# Sheet1.net
KiCad netlist of a schematic drawn in Altium Designer
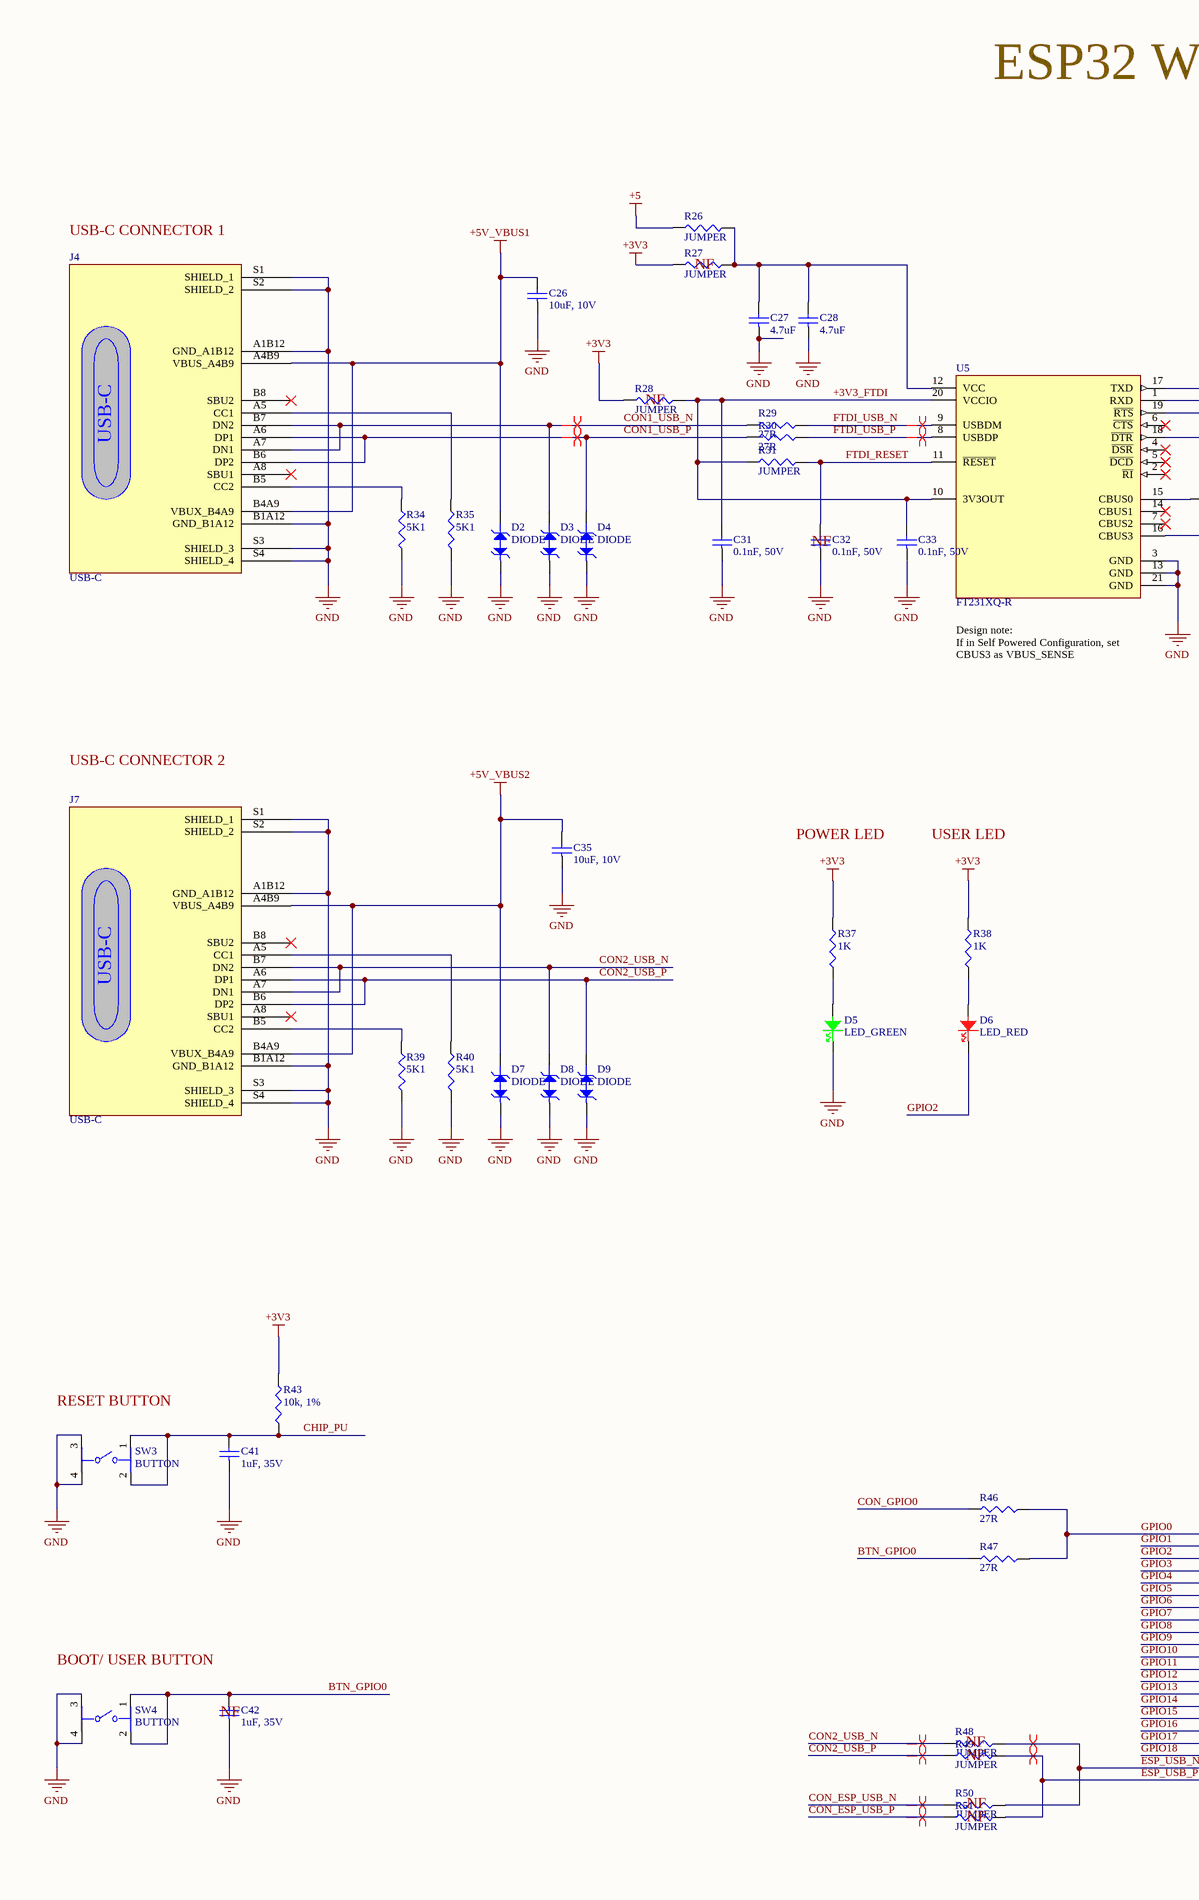
[diagram p0: Sheet1.SchDoc, left]
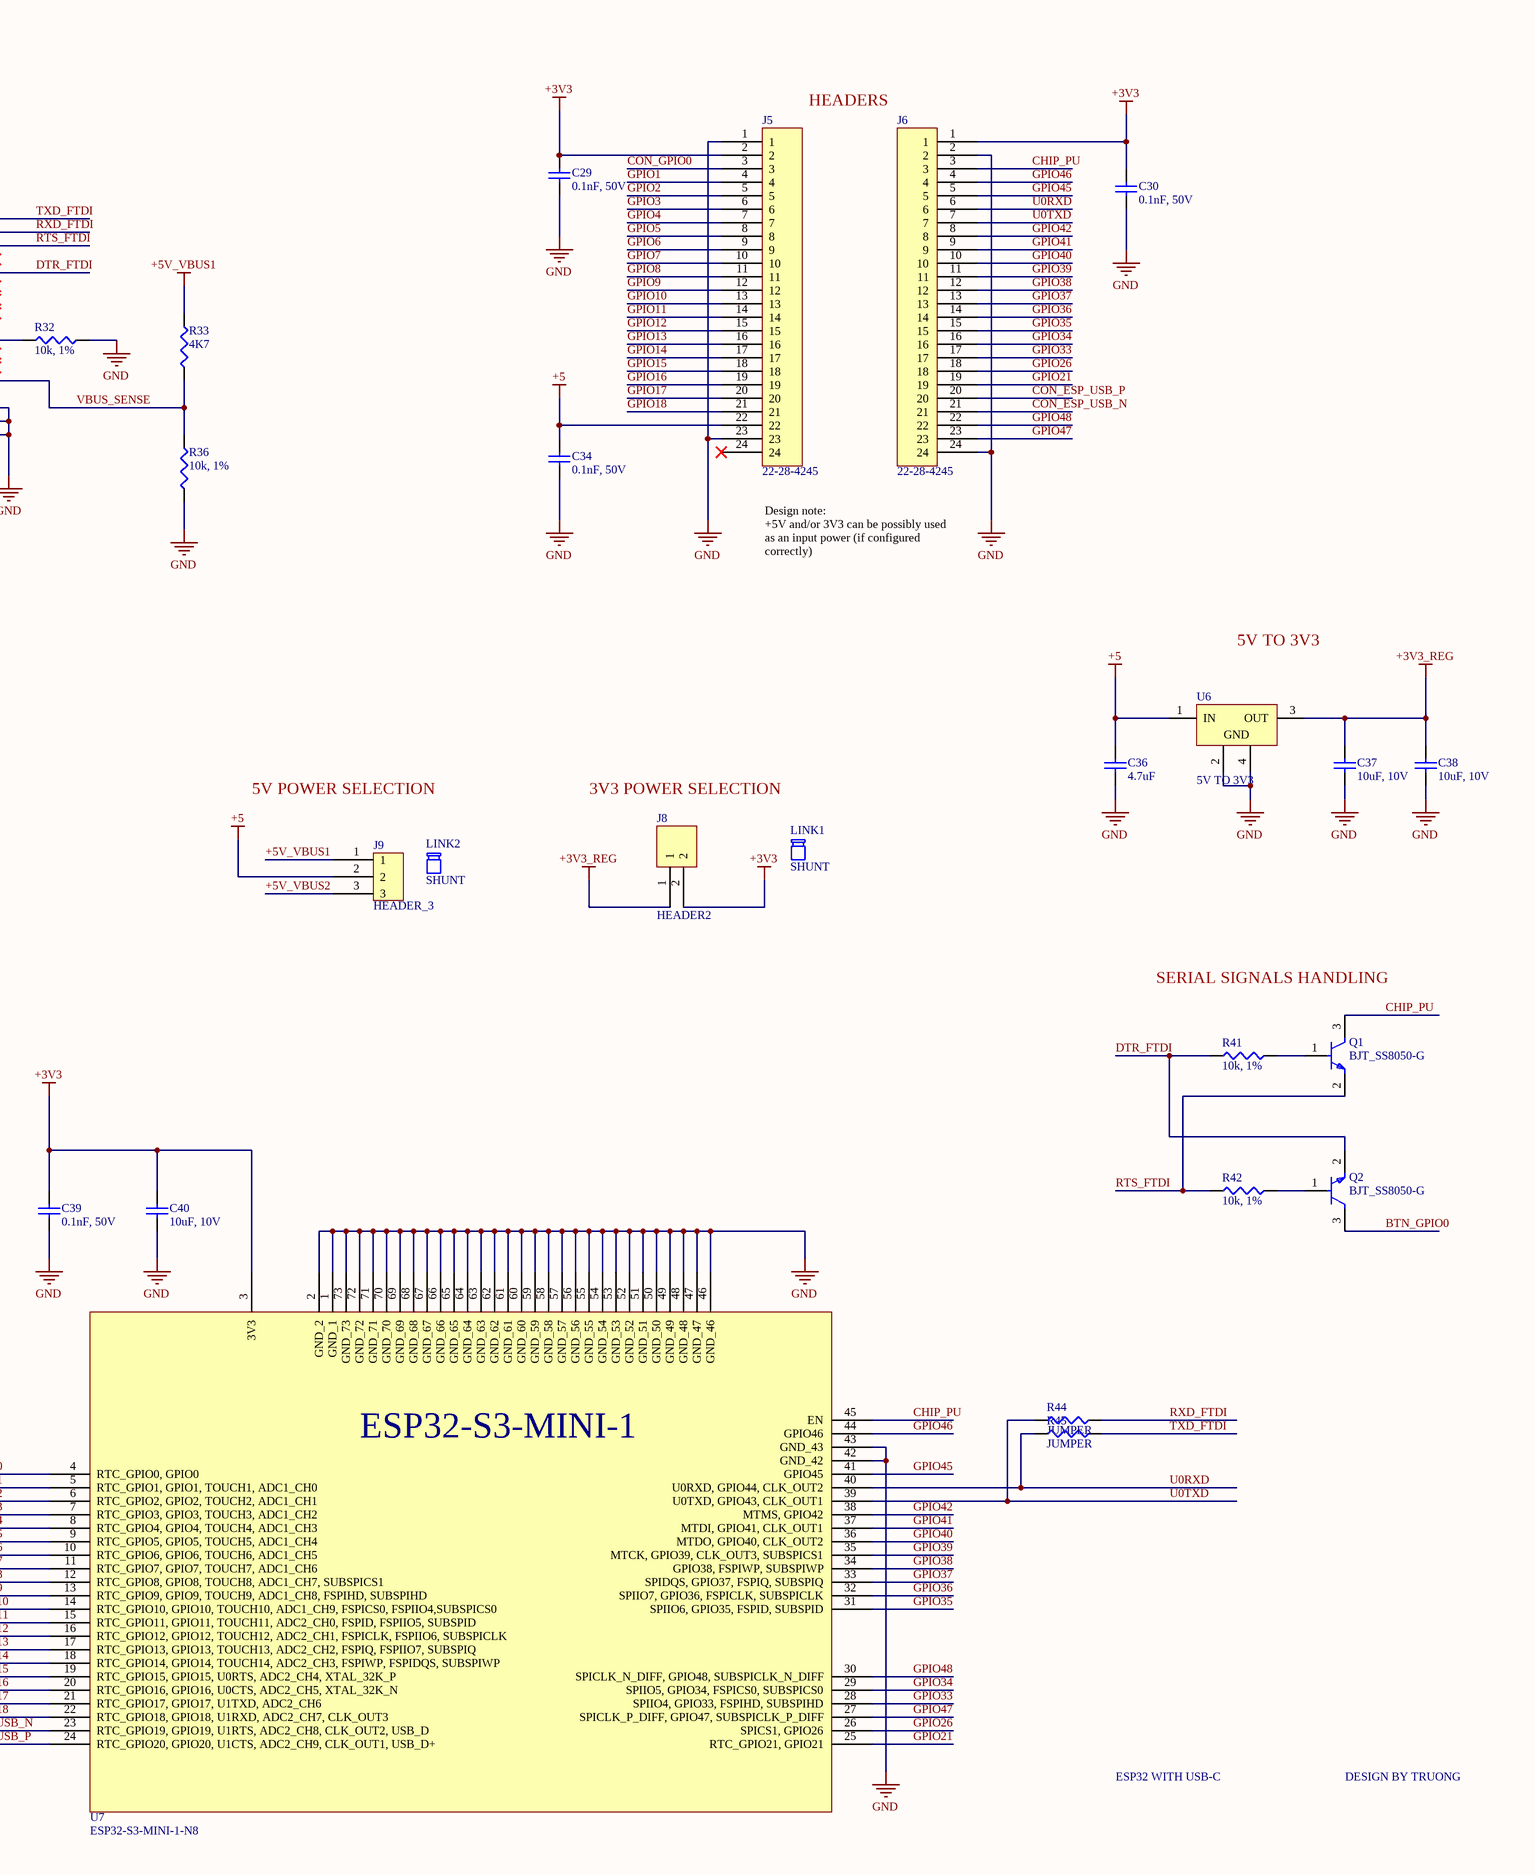
[diagram p1: Sheet1.SchDoc, right]

(export (version "E")
  (design (tool "Eeschema 10.0.6"))
  (components
    (comp (ref "C26")
      (value "10uF, 10V")
      (footprint "CAPC1005X70N")
      (description "CAP CER 10UF 10V X5R 0402")
      (fields
        (field (name "MANUFACTURER") "Samsung Electro-Mechanics")
        (field (name "MANUFACTURER PART NUMBER") "CL05A106MP5NUNC")
      )
      (libsource (lib "ESP32_CUSTOM_SCH.PrjPcb") (part "CL05A106MP5NUNC"))
    )
    (comp (ref "C27")
      (value "4.7uF")
      (footprint "CAPC1005X70N")
      (description "CAP CER 4.7UF 16V X5R 0402")
      (fields
        (field (name "MANUFACTURER") "Samsung Electro-Mechanics")
        (field (name "MANUFACTURER PART NUMBER") "CL05A475MO5NUNC")
      )
      (libsource (lib "ESP32_CUSTOM_SCH.PrjPcb") (part "CL05A475MO5NUNC"))
    )
    (comp (ref "C28")
      (value "4.7uF")
      (footprint "CAPC1005X70N")
      (description "CAP CER 4.7UF 16V X5R 0402")
      (fields
        (field (name "MANUFACTURER") "Samsung Electro-Mechanics")
        (field (name "MANUFACTURER PART NUMBER") "CL05A475MO5NUNC")
      )
      (libsource (lib "ESP32_CUSTOM_SCH.PrjPcb") (part "CL05A475MO5NUNC"))
    )
    (comp (ref "C29")
      (value "0.1nF, 50V")
      (footprint "CAPC1005X70N")
      (description "CAP CER 0.1UF 50V X7R 0402")
      (fields
        (field (name "MANUFACTURER") "Samsung Electro-Mechanics")
        (field (name "MANUFACTURER PART NUMBER") "CL05B104KB5NNWC")
      )
      (libsource (lib "ESP32_CUSTOM_SCH.PrjPcb") (part "CL05B104KB5NNWC"))
    )
    (comp (ref "C30")
      (value "0.1nF, 50V")
      (footprint "CAPC1005X70N")
      (description "CAP CER 0.1UF 50V X7R 0402")
      (fields
        (field (name "MANUFACTURER") "Samsung Electro-Mechanics")
        (field (name "MANUFACTURER PART NUMBER") "CL05B104KB5NNWC")
      )
      (libsource (lib "ESP32_CUSTOM_SCH.PrjPcb") (part "CL05B104KB5NNWC"))
    )
    (comp (ref "C31")
      (value "0.1nF, 50V")
      (footprint "CAPC1005X70N")
      (description "CAP CER 0.1UF 50V X7R 0402")
      (fields
        (field (name "MANUFACTURER") "Samsung Electro-Mechanics")
        (field (name "MANUFACTURER PART NUMBER") "CL05B104KB5NNWC")
      )
      (libsource (lib "ESP32_CUSTOM_SCH.PrjPcb") (part "CL05B104KB5NNWC"))
    )
    (comp (ref "C32")
      (value "0.1nF, 50V")
      (footprint "CAPC1005X70N")
      (description "CAP CER 0.1UF 50V X7R 0402")
      (fields
        (field (name "MANUFACTURER") "Samsung Electro-Mechanics")
        (field (name "MANUFACTURER PART NUMBER") "CL05B104KB5NNWC")
      )
      (libsource (lib "ESP32_CUSTOM_SCH.PrjPcb") (part "CL05B104KB5NNWC"))
    )
    (comp (ref "C33")
      (value "0.1nF, 50V")
      (footprint "CAPC1005X70N")
      (description "CAP CER 0.1UF 50V X7R 0402")
      (fields
        (field (name "MANUFACTURER") "Samsung Electro-Mechanics")
        (field (name "MANUFACTURER PART NUMBER") "CL05B104KB5NNWC")
      )
      (libsource (lib "ESP32_CUSTOM_SCH.PrjPcb") (part "CL05B104KB5NNWC"))
    )
    (comp (ref "C34")
      (value "0.1nF, 50V")
      (footprint "CAPC1005X70N")
      (description "CAP CER 0.1UF 50V X7R 0402")
      (fields
        (field (name "MANUFACTURER") "Samsung Electro-Mechanics")
        (field (name "MANUFACTURER PART NUMBER") "CL05B104KB5NNWC")
      )
      (libsource (lib "ESP32_CUSTOM_SCH.PrjPcb") (part "CL05B104KB5NNWC"))
    )
    (comp (ref "C35")
      (value "10uF, 10V")
      (footprint "CAPC1005X70N")
      (description "CAP CER 10UF 10V X5R 0402")
      (fields
        (field (name "MANUFACTURER") "Samsung Electro-Mechanics")
        (field (name "MANUFACTURER PART NUMBER") "CL05A106MP5NUNC")
      )
      (libsource (lib "ESP32_CUSTOM_SCH.PrjPcb") (part "CL05A106MP5NUNC"))
    )
    (comp (ref "C36")
      (value "4.7uF")
      (footprint "CAPC1005X70N")
      (description "CAP CER 4.7UF 16V X5R 0402")
      (fields
        (field (name "MANUFACTURER") "Samsung Electro-Mechanics")
        (field (name "MANUFACTURER PART NUMBER") "CL05A475MO5NUNC")
      )
      (libsource (lib "ESP32_CUSTOM_SCH.PrjPcb") (part "CL05A475MO5NUNC"))
    )
    (comp (ref "C37")
      (value "10uF, 10V")
      (footprint "CAPC1005X70N")
      (description "CAP CER 10UF 10V X5R 0402")
      (fields
        (field (name "MANUFACTURER") "Samsung Electro-Mechanics")
        (field (name "MANUFACTURER PART NUMBER") "CL05A106MP5NUNC")
      )
      (libsource (lib "ESP32_CUSTOM_SCH.PrjPcb") (part "CL05A106MP5NUNC"))
    )
    (comp (ref "C38")
      (value "10uF, 10V")
      (footprint "CAPC1005X70N")
      (description "CAP CER 10UF 10V X5R 0402")
      (fields
        (field (name "MANUFACTURER") "Samsung Electro-Mechanics")
        (field (name "MANUFACTURER PART NUMBER") "CL05A106MP5NUNC")
      )
      (libsource (lib "ESP32_CUSTOM_SCH.PrjPcb") (part "CL05A106MP5NUNC"))
    )
    (comp (ref "C39")
      (value "0.1nF, 50V")
      (footprint "CAPC1005X70N")
      (description "CAP CER 0.1UF 50V X7R 0402")
      (fields
        (field (name "MANUFACTURER") "Samsung Electro-Mechanics")
        (field (name "MANUFACTURER PART NUMBER") "CL05B104KB5NNWC")
      )
      (libsource (lib "ESP32_CUSTOM_SCH.PrjPcb") (part "CL05B104KB5NNWC"))
    )
    (comp (ref "C40")
      (value "10uF, 10V")
      (footprint "CAPC1005X70N")
      (description "CAP CER 10UF 10V X5R 0402")
      (fields
        (field (name "MANUFACTURER") "Samsung Electro-Mechanics")
        (field (name "MANUFACTURER PART NUMBER") "CL05A106MP5NUNC")
      )
      (libsource (lib "ESP32_CUSTOM_SCH.PrjPcb") (part "CL05A106MP5NUNC"))
    )
    (comp (ref "C41")
      (value "1uF, 35V")
      (footprint "CAPC1005X70N")
      (description "CAP CER 1UF 35V X5R 0402")
      (fields
        (field (name "MANUFACTURER") "Murata")
        (field (name "MANUFACTURER PART NUMBER") "GRM155R6YA105KE11D")
      )
      (libsource (lib "ESP32_CUSTOM_SCH.PrjPcb") (part "GRM155R6YA105KE11D"))
    )
    (comp (ref "C42")
      (value "1uF, 35V")
      (footprint "CAPC1005X70N")
      (description "CAP CER 1UF 35V X5R 0402")
      (fields
        (field (name "MANUFACTURER") "Murata")
        (field (name "MANUFACTURER PART NUMBER") "GRM155R6YA105KE11D")
      )
      (libsource (lib "ESP32_CUSTOM_SCH.PrjPcb") (part "GRM155R6YA105KE11D"))
    )
    (comp (ref "D2")
      (value "DIODE")
      (footprint "SOD882")
      (description "TVS DIODE 5.3VWM 12VC SOD882")
      (fields
        (field (name "MANUFACTURER") "Littelfuse")
        (field (name "MANUFACTURER PART NUMBER") "AQ3045-01ETG")
      )
      (libsource (lib "ESP32_CUSTOM_SCH.PrjPcb") (part "AQ3045-01ETG"))
    )
    (comp (ref "D3")
      (value "DIODE")
      (footprint "SOD882")
      (description "TVS DIODE 5.3VWM 12VC SOD882")
      (fields
        (field (name "MANUFACTURER") "Littelfuse")
        (field (name "MANUFACTURER PART NUMBER") "AQ3045-01ETG")
      )
      (libsource (lib "ESP32_CUSTOM_SCH.PrjPcb") (part "AQ3045-01ETG"))
    )
    (comp (ref "D4")
      (value "DIODE")
      (footprint "SOD882")
      (description "TVS DIODE 5.3VWM 12VC SOD882")
      (fields
        (field (name "MANUFACTURER") "Littelfuse")
        (field (name "MANUFACTURER PART NUMBER") "AQ3045-01ETG")
      )
      (libsource (lib "ESP32_CUSTOM_SCH.PrjPcb") (part "AQ3045-01ETG"))
    )
    (comp (ref "D5")
      (value "LED_GREEN")
      (footprint "LED0402_GREEN")
      (description "LED GREEN 0402 SMD")
      (fields
        (field (name "MANUFACTURER") "Vishay")
        (field (name "MANUFACTURER PART NUMBER") "VLMTG1500-GS08")
      )
      (libsource (lib "ESP32_CUSTOM_SCH.PrjPcb") (part "VLMTG1500-GS08"))
    )
    (comp (ref "D6")
      (value "LED_RED")
      (footprint "LED0402_RED")
      (description "LED RED 0402 SMD")
      (fields
        (field (name "MANUFACTURER") "Vishay")
        (field (name "MANUFACTURER PART NUMBER") "VLMS1500-GS08")
      )
      (libsource (lib "ESP32_CUSTOM_SCH.PrjPcb") (part "VLMS1500-GS08"))
    )
    (comp (ref "D7")
      (value "DIODE")
      (footprint "SOD882")
      (description "TVS DIODE 5.3VWM 12VC SOD882")
      (fields
        (field (name "MANUFACTURER") "Littelfuse")
        (field (name "MANUFACTURER PART NUMBER") "AQ3045-01ETG")
      )
      (libsource (lib "ESP32_CUSTOM_SCH.PrjPcb") (part "AQ3045-01ETG"))
    )
    (comp (ref "D8")
      (value "DIODE")
      (footprint "SOD882")
      (description "TVS DIODE 5.3VWM 12VC SOD882")
      (fields
        (field (name "MANUFACTURER") "Littelfuse")
        (field (name "MANUFACTURER PART NUMBER") "AQ3045-01ETG")
      )
      (libsource (lib "ESP32_CUSTOM_SCH.PrjPcb") (part "AQ3045-01ETG"))
    )
    (comp (ref "D9")
      (value "DIODE")
      (footprint "SOD882")
      (description "TVS DIODE 5.3VWM 12VC SOD882")
      (fields
        (field (name "MANUFACTURER") "Littelfuse")
        (field (name "MANUFACTURER PART NUMBER") "AQ3045-01ETG")
      )
      (libsource (lib "ESP32_CUSTOM_SCH.PrjPcb") (part "AQ3045-01ETG"))
    )
    (comp (ref "J4")
      (value "USB-C")
      (footprint "FP-2171790001-MFG")
      (description "CONN RCP USB2.0 TYP C 24P SMD RA")
      (fields (field (name "MANUFACTURER") "Molex") (field (name "MANUFACTURER PART NUMBER") "217179-0001"))
      (libsource (lib "ESP32_CUSTOM_SCH.PrjPcb") (part "217179-0001"))
    )
    (comp (ref "J5")
      (value "22-28-4245")
      (footprint "HDR_1X24_2.55MM")
      (description "CONN HEADER VERT 24POS 2.54MM")
      (fields (field (name "MANUFACTURER") "Molex") (field (name "LCSC PART NUMBER") "C7145888"))
      (libsource (lib "") (part "22-28-4245_1"))
    )
    (comp (ref "J6")
      (value "22-28-4245")
      (footprint "HDR_1X24_2.55MM")
      (description "CONN HEADER VERT 24POS 2.54MM")
      (fields (field (name "MANUFACTURER") "Molex") (field (name "LCSC PART NUMBER") "C7145888"))
      (libsource (lib "ESP32_CUSTOM_SCH.PrjPcb") (part "22-28-4245"))
    )
    (comp (ref "J7")
      (value "USB-C")
      (footprint "FP-2171790001-MFG")
      (description "CONN RCP USB2.0 TYP C 24P SMD RA")
      (fields (field (name "MANUFACTURER") "Molex") (field (name "MANUFACTURER PART NUMBER") "217179-0001"))
      (libsource (lib "ESP32_CUSTOM_SCH.PrjPcb") (part "217179-0001"))
    )
    (comp (ref "J8")
      (value "HEADER2")
      (footprint "HDR_1X2_1.27MM")
      (description "CONN HEADER VERT 2POS 1.27MM")
      (fields
        (field (name "MANUFACTURER") "Samtec")
        (field (name "MANUFACTURER PART NUMBER") "FTS-102-01-L-S")
      )
      (libsource (lib "ESP32_CUSTOM_SCH.PrjPcb") (part "FTS-102-01-L-S"))
    )
    (comp (ref "J9")
      (value "HEADER_3")
      (footprint "HDR_1X3_1.27MM")
      (description "CONN HEADER VERT 3POS 1.27MM")
      (fields
        (field (name "MANUFACTURER") "Samtec")
        (field (name "MANUFACTURER PART NUMBER") "FTS-103-01-F-S")
      )
      (libsource (lib "ESP32_CUSTOM_SCH.PrjPcb") (part "FTS-103-01-F-S"))
    )
    (comp (ref "LINK1")
      (value "SHUNT")
      (description "CONN SHUNT 1.27MM RED")
      (fields (field (name "MANUFACTURER") "Harwin") (field (name "MANUFACTURER PART NUMBER") "M50-1920005"))
      (libsource (lib "ESP32_CUSTOM_SCH.PrjPcb") (part "M50-1920005"))
    )
    (comp (ref "LINK2")
      (value "SHUNT")
      (description "CONN SHUNT 1.27MM RED")
      (fields (field (name "MANUFACTURER") "Harwin") (field (name "MANUFACTURER PART NUMBER") "M50-1920005"))
      (libsource (lib "ESP32_CUSTOM_SCH.PrjPcb") (part "M50-1920005"))
    )
    (comp (ref "Q1")
      (value "BJT_SS8050-G")
      (footprint "FP-SS8050-G-IPC_B")
      (description "TRANS NPN 25V 1.5A SOT-23-3")
      (fields (field (name "MANUFACTURER") "Comchip") (field (name "MANUFACTURER PART NUMBER") "SS8050-G"))
      (libsource (lib "ESP32_CUSTOM_SCH.PrjPcb") (part "SS8050-G"))
    )
    (comp (ref "Q2")
      (value "BJT_SS8050-G")
      (footprint "FP-SS8050-G-IPC_B")
      (description "TRANS NPN 25V 1.5A SOT-23-3")
      (fields (field (name "MANUFACTURER") "Comchip") (field (name "MANUFACTURER PART NUMBER") "SS8050-G"))
      (libsource (lib "ESP32_CUSTOM_SCH.PrjPcb") (part "SS8050-G"))
    )
    (comp (ref "R26")
      (value "JUMPER")
      (footprint "RESC1005X40N")
      (description "RES 0 OHM JUMPER 1/16W 0402")
      (fields
        (field (name "MANUFACTURER") "Yageo Group")
        (field (name "MANUFACTURER PART NUMBER") "RC0402JR-070RL")
      )
      (libsource (lib "ESP32_CUSTOM_SCH.PrjPcb") (part "RC0402JR-070RL"))
    )
    (comp (ref "R27")
      (value "JUMPER")
      (footprint "RESC1005X40N")
      (description "RES 0 OHM JUMPER 1/16W 0402")
      (fields
        (field (name "MANUFACTURER") "Yageo Group")
        (field (name "MANUFACTURER PART NUMBER") "RC0402JR-070RL")
      )
      (libsource (lib "ESP32_CUSTOM_SCH.PrjPcb") (part "RC0402JR-070RL"))
    )
    (comp (ref "R28")
      (value "JUMPER")
      (footprint "RESC1005X40N")
      (description "RES 0 OHM JUMPER 1/16W 0402")
      (fields
        (field (name "MANUFACTURER") "Yageo Group")
        (field (name "MANUFACTURER PART NUMBER") "RC0402JR-070RL")
      )
      (libsource (lib "ESP32_CUSTOM_SCH.PrjPcb") (part "RC0402JR-070RL"))
    )
    (comp (ref "R29")
      (value "27R")
      (footprint "RESC1005X40N")
      (description "RES 27 OHM 1% 1/16W 0402")
      (fields
        (field (name "MANUFACTURER") "Yageo Group")
        (field (name "MANUFACTURER PART NUMBER") "RC0402FR-0727RL")
      )
      (libsource (lib "ESP32_CUSTOM_SCH.PrjPcb") (part "RC0402FR-0727RL"))
    )
    (comp (ref "R30")
      (value "27R")
      (footprint "RESC1005X40N")
      (description "RES 27 OHM 1% 1/16W 0402")
      (fields
        (field (name "MANUFACTURER") "Yageo Group")
        (field (name "MANUFACTURER PART NUMBER") "RC0402FR-0727RL")
      )
      (libsource (lib "ESP32_CUSTOM_SCH.PrjPcb") (part "RC0402FR-0727RL"))
    )
    (comp (ref "R31")
      (value "JUMPER")
      (footprint "RESC1005X40N")
      (description "RES 0 OHM JUMPER 1/16W 0402")
      (fields
        (field (name "MANUFACTURER") "Yageo Group")
        (field (name "MANUFACTURER PART NUMBER") "RC0402JR-070RL")
      )
      (libsource (lib "ESP32_CUSTOM_SCH.PrjPcb") (part "RC0402JR-070RL"))
    )
    (comp (ref "R32")
      (value "10k, 1%")
      (footprint "RESC1005X40N")
      (description "RES 10K OHM 1% 1/16W 0402")
      (fields
        (field (name "MANUFACTURER") "Yageo Group")
        (field (name "MANUFACTURER PART NUMBER") "RC0402FR-0710KL")
      )
      (libsource (lib "ESP32_CUSTOM_SCH.PrjPcb") (part "RC0402FR-0710KL"))
    )
    (comp (ref "R33")
      (value "4K7")
      (footprint "RESC1005X40N")
      (description "RES 4.7K OHM 1% 1/16W 0402")
      (fields
        (field (name "MANUFACTURER") "Yageo Group")
        (field (name "MANUFACTURER PART NUMBER") "RC0402FR-074K7L")
      )
      (libsource (lib "ESP32_CUSTOM_SCH.PrjPcb") (part "RC0402FR-074K7L"))
    )
    (comp (ref "R34")
      (value "5K1")
      (footprint "RESC1005X40N")
      (description "RES 5.1K OHM 1% 1/16W 0402")
      (fields
        (field (name "MANUFACTURER") "Yageo Group")
        (field (name "MANUFACTURER PART NUMBER") "RC0402FR-07510KL")
      )
      (libsource (lib "ESP32_CUSTOM_SCH.PrjPcb") (part "RC0402FR-07510KL"))
    )
    (comp (ref "R35")
      (value "5K1")
      (footprint "RESC1005X40N")
      (description "RES 5.1K OHM 1% 1/16W 0402")
      (fields
        (field (name "MANUFACTURER") "Yageo Group")
        (field (name "MANUFACTURER PART NUMBER") "RC0402FR-07510KL")
      )
      (libsource (lib "ESP32_CUSTOM_SCH.PrjPcb") (part "RC0402FR-07510KL"))
    )
    (comp (ref "R36")
      (value "10k, 1%")
      (footprint "RESC1005X40N")
      (description "RES 10K OHM 1% 1/16W 0402")
      (fields
        (field (name "MANUFACTURER") "Yageo Group")
        (field (name "MANUFACTURER PART NUMBER") "RC0402FR-0710KL")
      )
      (libsource (lib "ESP32_CUSTOM_SCH.PrjPcb") (part "RC0402FR-0710KL"))
    )
    (comp (ref "R37")
      (value "1K")
      (footprint "RESC1005X40N")
      (description "RES 1K OHM 5% 1/16W 0402")
      (fields
        (field (name "MANUFACTURER") "Yageo Group")
        (field (name "MANUFACTURER PART NUMBER") "RC0402JR-071KL")
      )
      (libsource (lib "ESP32_CUSTOM_SCH.PrjPcb") (part "RC0402JR-071KL"))
    )
    (comp (ref "R38")
      (value "1K")
      (footprint "RESC1005X40N")
      (description "RES 1K OHM 5% 1/16W 0402")
      (fields
        (field (name "MANUFACTURER") "Yageo Group")
        (field (name "MANUFACTURER PART NUMBER") "RC0402JR-071KL")
      )
      (libsource (lib "ESP32_CUSTOM_SCH.PrjPcb") (part "RC0402JR-071KL"))
    )
    (comp (ref "R39")
      (value "5K1")
      (footprint "RESC1005X40N")
      (description "RES 5.1K OHM 1% 1/16W 0402")
      (fields
        (field (name "MANUFACTURER") "Yageo Group")
        (field (name "MANUFACTURER PART NUMBER") "RC0402FR-07510KL")
      )
      (libsource (lib "ESP32_CUSTOM_SCH.PrjPcb") (part "RC0402FR-07510KL"))
    )
    (comp (ref "R40")
      (value "5K1")
      (footprint "RESC1005X40N")
      (description "RES 5.1K OHM 1% 1/16W 0402")
      (fields
        (field (name "MANUFACTURER") "Yageo Group")
        (field (name "MANUFACTURER PART NUMBER") "RC0402FR-07510KL")
      )
      (libsource (lib "ESP32_CUSTOM_SCH.PrjPcb") (part "RC0402FR-07510KL"))
    )
    (comp (ref "R41")
      (value "10k, 1%")
      (footprint "RESC1005X40N")
      (description "RES 10K OHM 1% 1/16W 0402")
      (fields
        (field (name "MANUFACTURER") "Yageo Group")
        (field (name "MANUFACTURER PART NUMBER") "RC0402FR-0710KL")
      )
      (libsource (lib "ESP32_CUSTOM_SCH.PrjPcb") (part "RC0402FR-0710KL"))
    )
    (comp (ref "R42")
      (value "10k, 1%")
      (footprint "RESC1005X40N")
      (description "RES 10K OHM 1% 1/16W 0402")
      (fields
        (field (name "MANUFACTURER") "Yageo Group")
        (field (name "MANUFACTURER PART NUMBER") "RC0402FR-0710KL")
      )
      (libsource (lib "ESP32_CUSTOM_SCH.PrjPcb") (part "RC0402FR-0710KL"))
    )
    (comp (ref "R43")
      (value "10k, 1%")
      (footprint "RESC1005X40N")
      (description "RES 10K OHM 1% 1/16W 0402")
      (fields
        (field (name "MANUFACTURER") "Yageo Group")
        (field (name "MANUFACTURER PART NUMBER") "RC0402FR-0710KL")
      )
      (libsource (lib "ESP32_CUSTOM_SCH.PrjPcb") (part "RC0402FR-0710KL"))
    )
    (comp (ref "R44")
      (value "JUMPER")
      (footprint "RESC1005X40N")
      (description "RES 0 OHM JUMPER 1/16W 0402")
      (fields
        (field (name "MANUFACTURER") "Yageo Group")
        (field (name "MANUFACTURER PART NUMBER") "RC0402JR-070RL")
      )
      (libsource (lib "ESP32_CUSTOM_SCH.PrjPcb") (part "RC0402JR-070RL"))
    )
    (comp (ref "R45")
      (value "JUMPER")
      (footprint "RESC1005X40N")
      (description "RES 0 OHM JUMPER 1/16W 0402")
      (fields
        (field (name "MANUFACTURER") "Yageo Group")
        (field (name "MANUFACTURER PART NUMBER") "RC0402JR-070RL")
      )
      (libsource (lib "ESP32_CUSTOM_SCH.PrjPcb") (part "RC0402JR-070RL"))
    )
    (comp (ref "R46")
      (value "27R")
      (footprint "RESC1005X40N")
      (description "RES 27 OHM 1% 1/16W 0402")
      (fields
        (field (name "MANUFACTURER") "Yageo Group")
        (field (name "MANUFACTURER PART NUMBER") "RC0402FR-0727RL")
      )
      (libsource (lib "ESP32_CUSTOM_SCH.PrjPcb") (part "RC0402FR-0727RL"))
    )
    (comp (ref "R47")
      (value "27R")
      (footprint "RESC1005X40N")
      (description "RES 27 OHM 1% 1/16W 0402")
      (fields
        (field (name "MANUFACTURER") "Yageo Group")
        (field (name "MANUFACTURER PART NUMBER") "RC0402FR-0727RL")
      )
      (libsource (lib "ESP32_CUSTOM_SCH.PrjPcb") (part "RC0402FR-0727RL"))
    )
    (comp (ref "R48")
      (value "JUMPER")
      (footprint "RESC1005X40N")
      (description "RES 0 OHM JUMPER 1/16W 0402")
      (fields
        (field (name "MANUFACTURER") "Yageo Group")
        (field (name "MANUFACTURER PART NUMBER") "RC0402JR-070RL")
      )
      (libsource (lib "ESP32_CUSTOM_SCH.PrjPcb") (part "RC0402JR-070RL"))
    )
    (comp (ref "R49")
      (value "JUMPER")
      (footprint "RESC1005X40N")
      (description "RES 0 OHM JUMPER 1/16W 0402")
      (fields
        (field (name "MANUFACTURER") "Yageo Group")
        (field (name "MANUFACTURER PART NUMBER") "RC0402JR-070RL")
      )
      (libsource (lib "ESP32_CUSTOM_SCH.PrjPcb") (part "RC0402JR-070RL"))
    )
    (comp (ref "R50")
      (value "JUMPER")
      (footprint "RESC1005X40N")
      (description "RES 0 OHM JUMPER 1/16W 0402")
      (fields
        (field (name "MANUFACTURER") "Yageo Group")
        (field (name "MANUFACTURER PART NUMBER") "RC0402JR-070RL")
      )
      (libsource (lib "ESP32_CUSTOM_SCH.PrjPcb") (part "RC0402JR-070RL"))
    )
    (comp (ref "R51")
      (value "JUMPER")
      (footprint "RESC1005X40N")
      (description "RES 0 OHM JUMPER 1/16W 0402")
      (fields
        (field (name "MANUFACTURER") "Yageo Group")
        (field (name "MANUFACTURER PART NUMBER") "RC0402JR-070RL")
      )
      (libsource (lib "ESP32_CUSTOM_SCH.PrjPcb") (part "RC0402JR-070RL"))
    )
    (comp (ref "SW3")
      (value "BUTTON")
      (footprint "FP-PTS645SM43SMTR92LFS-MFG")
      (description "SWITCH TACTILE SPST-NO 0.05A 12V")
      (fields
        (field (name "MANUFACTURER") "C&K Components")
        (field (name "MANUFACTURER PART NUMBER") "PTS645SM43SMTR92LFS")
      )
      (libsource (lib "ESP32_CUSTOM_SCH.PrjPcb") (part "PTS645SM43SMTR92LFS"))
    )
    (comp (ref "SW4")
      (value "BUTTON")
      (footprint "FP-PTS645SM43SMTR92LFS-MFG")
      (description "SWITCH TACTILE SPST-NO 0.05A 12V")
      (fields
        (field (name "MANUFACTURER") "C&K Components")
        (field (name "MANUFACTURER PART NUMBER") "PTS645SM43SMTR92LFS")
      )
      (libsource (lib "ESP32_CUSTOM_SCH.PrjPcb") (part "PTS645SM43SMTR92LFS"))
    )
    (comp (ref "U5")
      (value "FT231XQ-R")
      (footprint "FP-QFN-20-IPC_B")
      (description "IC USB SERIAL FULL UART 20QFN")
      (fields (field (name "MANUFACTURER") "FTDI") (field (name "LCSC PART NUMBER") "C132159"))
      (libsource (lib "ESP32_CUSTOM_SCH.PrjPcb") (part "FT231XQ-R"))
    )
    (comp (ref "U6")
      (value "5V TO 3V3")
      (footprint "DCY0004A_N")
      (description "IC REG LIN 3.3V 1.5A SOT-223-4")
      (fields
        (field (name "MANUFACTURER") "Texas Instruments")
        (field (name "MANUFACTURER PART NUMBER") "TL1963A-33DCYR")
      )
      (libsource (lib "ESP32_CUSTOM_SCH.PrjPcb") (part "TL1963A-33DCYR"))
    )
    (comp (ref "U7")
      (value "ESP32-S3-MINI-1-N8")
      (footprint "XCVR_ESP32-S3-MINI-1-N8")
      (description "20.5dBm ESP32-S3FN8 Chip 2.4GHz SMD WiFi Modules ROHS")
      (fields (field (name "MANUFACTURER") "Espressif Systems") (field (name "LCSC PART NUMBER") "C2913206"))
      (libsource (lib "ESP32_CUSTOM_SCH.PrjPcb") (part "ESP32-S3-MINI-1-N8 (2)"))
    )
  )
  (nets
    (net (code "1") (name "+3V3") (class "Default")
      (node (ref "C29") (pin "2") (pinfunction "2_2") (pintype "passive"))
      (node (ref "C30") (pin "2") (pinfunction "2_2") (pintype "passive"))
      (node (ref "C39") (pin "2") (pinfunction "2_2") (pintype "passive"))
      (node (ref "C40") (pin "2") (pinfunction "2_2") (pintype "passive"))
      (node (ref "J5") (pin "2") (pinfunction "2_2") (pintype "passive"))
      (node (ref "J6") (pin "1") (pinfunction "1_1") (pintype "passive"))
      (node (ref "J8") (pin "2") (pinfunction "2_2") (pintype "passive"))
      (node (ref "R27") (pin "1") (pinfunction "1_1") (pintype "passive"))
      (node (ref "R28") (pin "1") (pinfunction "1_1") (pintype "passive"))
      (node (ref "R37") (pin "2") (pinfunction "2_2") (pintype "passive"))
      (node (ref "R38") (pin "2") (pinfunction "2_2") (pintype "passive"))
      (node (ref "R43") (pin "2") (pinfunction "2_2") (pintype "passive"))
      (node (ref "U7") (pin "3") (pinfunction "3V3_3") (pintype "passive"))
    )
    (net (code "2") (name "+3V3_REG") (class "Default")
      (node (ref "C37") (pin "2") (pinfunction "2_2") (pintype "passive"))
      (node (ref "C38") (pin "2") (pinfunction "2_2") (pintype "passive"))
      (node (ref "J8") (pin "1") (pinfunction "1_1") (pintype "passive"))
      (node (ref "U6") (pin "3") (pinfunction "OUT_3") (pintype "power_in"))
    )
    (net (code "3") (name "+5") (class "Default")
      (node (ref "C34") (pin "2") (pinfunction "2_2") (pintype "passive"))
      (node (ref "C36") (pin "2") (pinfunction "2_2") (pintype "passive"))
      (node (ref "J5") (pin "22") (pinfunction "22_22") (pintype "passive"))
      (node (ref "J9") (pin "2") (pinfunction "2_2") (pintype "passive"))
      (node (ref "R26") (pin "1") (pinfunction "1_1") (pintype "passive"))
      (node (ref "U6") (pin "1") (pinfunction "IN_1") (pintype "power_in"))
    )
    (net (code "4") (name "+5V_VBUS1") (class "Default")
      (node (ref "C26") (pin "2") (pinfunction "2_2") (pintype "passive"))
      (node (ref "D2") (pin "2") (pinfunction "2_2") (pintype "passive"))
      (node (ref "J4") (pin "A4B9") (pinfunction "VBUS_A4B9_A4B9") (pintype "passive"))
      (node (ref "J4") (pin "B4A9") (pinfunction "VBUX_B4A9_B4A9") (pintype "passive"))
      (node (ref "J9") (pin "1") (pinfunction "1_1") (pintype "passive"))
      (node (ref "R33") (pin "2") (pinfunction "2_2") (pintype "passive"))
    )
    (net (code "5") (name "+5V_VBUS2") (class "Default")
      (node (ref "C35") (pin "2") (pinfunction "2_2") (pintype "passive"))
      (node (ref "D7") (pin "2") (pinfunction "2_2") (pintype "passive"))
      (node (ref "J7") (pin "A4B9") (pinfunction "VBUS_A4B9_A4B9") (pintype "passive"))
      (node (ref "J7") (pin "B4A9") (pinfunction "VBUX_B4A9_B4A9") (pintype "passive"))
      (node (ref "J9") (pin "3") (pinfunction "3_3") (pintype "passive"))
    )
    (net (code "6") (name "/+3V3_FTDI") (class "Default")
      (node (ref "C31") (pin "2") (pinfunction "2_2") (pintype "passive"))
      (node (ref "C33") (pin "2") (pinfunction "2_2") (pintype "passive"))
      (node (ref "R28") (pin "2") (pinfunction "2_2") (pintype "passive"))
      (node (ref "R31") (pin "1") (pinfunction "1_1") (pintype "passive"))
      (node (ref "U5") (pin "10") (pinfunction "3V3OUT_10") (pintype "passive"))
      (node (ref "U5") (pin "20") (pinfunction "VCCIO_20") (pintype "passive"))
    )
    (net (code "7") (name "/BTN_GPIO0") (class "Default")
      (node (ref "C42") (pin "2") (pinfunction "2_2") (pintype "passive"))
      (node (ref "Q2") (pin "3") (pinfunction "C_3") (pintype "passive"))
      (node (ref "R47") (pin "1") (pinfunction "1_1") (pintype "passive"))
      (node (ref "SW4") (pin "1") (pinfunction "1_1") (pintype "passive"))
      (node (ref "SW4") (pin "2") (pinfunction "2_2") (pintype "passive"))
    )
    (net (code "8") (name "/CHIP_PU") (class "Default")
      (node (ref "C41") (pin "2") (pinfunction "2_2") (pintype "passive"))
      (node (ref "J6") (pin "3") (pinfunction "3_3") (pintype "passive"))
      (node (ref "Q1") (pin "3") (pinfunction "C_3") (pintype "passive"))
      (node (ref "R43") (pin "1") (pinfunction "1_1") (pintype "passive"))
      (node (ref "SW3") (pin "1") (pinfunction "1_1") (pintype "passive"))
      (node (ref "SW3") (pin "2") (pinfunction "2_2") (pintype "passive"))
      (node (ref "U7") (pin "45") (pinfunction "EN_45") (pintype "passive"))
    )
    (net (code "9") (name "/CON1_USB_N") (class "Default")
      (node (ref "D3") (pin "2") (pinfunction "2_2") (pintype "passive"))
      (node (ref "J4") (pin "A7") (pinfunction "DN1_A7") (pintype "passive"))
      (node (ref "J4") (pin "B7") (pinfunction "DN2_B7") (pintype "passive"))
      (node (ref "R29") (pin "1") (pinfunction "1_1") (pintype "passive"))
    )
    (net (code "10") (name "/CON1_USB_P") (class "Default")
      (node (ref "D4") (pin "2") (pinfunction "2_2") (pintype "passive"))
      (node (ref "J4") (pin "A6") (pinfunction "DP1_A6") (pintype "passive"))
      (node (ref "J4") (pin "B6") (pinfunction "DP2_B6") (pintype "passive"))
      (node (ref "R30") (pin "1") (pinfunction "1_1") (pintype "passive"))
    )
    (net (code "11") (name "/CON2_USB_N") (class "Default")
      (node (ref "D8") (pin "2") (pinfunction "2_2") (pintype "passive"))
      (node (ref "J7") (pin "A7") (pinfunction "DN1_A7") (pintype "passive"))
      (node (ref "J7") (pin "B7") (pinfunction "DN2_B7") (pintype "passive"))
      (node (ref "R48") (pin "1") (pinfunction "1_1") (pintype "passive"))
    )
    (net (code "12") (name "/CON2_USB_P") (class "Default")
      (node (ref "D9") (pin "2") (pinfunction "2_2") (pintype "passive"))
      (node (ref "J7") (pin "A6") (pinfunction "DP1_A6") (pintype "passive"))
      (node (ref "J7") (pin "B6") (pinfunction "DP2_B6") (pintype "passive"))
      (node (ref "R49") (pin "1") (pinfunction "1_1") (pintype "passive"))
    )
    (net (code "13") (name "/CON_ESP_USB_N") (class "Default")
      (node (ref "J6") (pin "21") (pinfunction "21_21") (pintype "passive"))
      (node (ref "R50") (pin "1") (pinfunction "1_1") (pintype "passive"))
    )
    (net (code "14") (name "/CON_ESP_USB_P") (class "Default")
      (node (ref "J6") (pin "20") (pinfunction "20_20") (pintype "passive"))
      (node (ref "R51") (pin "1") (pinfunction "1_1") (pintype "passive"))
    )
    (net (code "15") (name "/CON_GPIO0") (class "Default")
      (node (ref "J5") (pin "3") (pinfunction "3_3") (pintype "passive"))
      (node (ref "R46") (pin "1") (pinfunction "1_1") (pintype "passive"))
    )
    (net (code "16") (name "/DTR_FTDI") (class "Default")
      (node (ref "Q2") (pin "2") (pinfunction "E_2") (pintype "passive"))
      (node (ref "R41") (pin "1") (pinfunction "1_1") (pintype "passive"))
      (node (ref "U5") (pin "18") (pinfunction "~{DTR}_18") (pintype "output"))
    )
    (net (code "17") (name "/ESP_USB_N") (class "Default")
      (node (ref "R48") (pin "2") (pinfunction "2_2") (pintype "passive"))
      (node (ref "R50") (pin "2") (pinfunction "2_2") (pintype "passive"))
      (node (ref "U7") (pin "23") (pinfunction "RTC_GPIO19,_GPIO19,_U1RTS,_ADC2_CH8,_CLK_OUT2,_USB_D_23") (pintype "passive"))
    )
    (net (code "18") (name "/ESP_USB_P") (class "Default")
      (node (ref "R49") (pin "2") (pinfunction "2_2") (pintype "passive"))
      (node (ref "R51") (pin "2") (pinfunction "2_2") (pintype "passive"))
      (node (ref "U7") (pin "24") (pinfunction "RTC_GPIO20,_GPIO20,_U1CTS,_ADC2_CH9,_CLK_OUT1,_USB_D+_24") (pintype "passive"))
    )
    (net (code "19") (name "/FTDI_RESET") (class "Default")
      (node (ref "C32") (pin "2") (pinfunction "2_2") (pintype "passive"))
      (node (ref "R31") (pin "2") (pinfunction "2_2") (pintype "passive"))
      (node (ref "U5") (pin "11") (pinfunction "~{RESET}_11") (pintype "passive"))
    )
    (net (code "20") (name "/FTDI_USB_N") (class "Default")
      (node (ref "R29") (pin "2") (pinfunction "2_2") (pintype "passive"))
      (node (ref "U5") (pin "9") (pinfunction "USBDM_9") (pintype "passive"))
    )
    (net (code "21") (name "/FTDI_USB_P") (class "Default")
      (node (ref "R30") (pin "2") (pinfunction "2_2") (pintype "passive"))
      (node (ref "U5") (pin "8") (pinfunction "USBDP_8") (pintype "passive"))
    )
    (net (code "22") (name "/GPIO0") (class "Default")
      (node (ref "R46") (pin "2") (pinfunction "2_2") (pintype "passive"))
      (node (ref "R47") (pin "2") (pinfunction "2_2") (pintype "passive"))
      (node (ref "U7") (pin "4") (pinfunction "RTC_GPIO0,_GPIO0_4") (pintype "passive"))
    )
    (net (code "23") (name "/GPIO1") (class "Default")
      (node (ref "J5") (pin "4") (pinfunction "4_4") (pintype "passive"))
      (node (ref "U7") (pin "5") (pinfunction "RTC_GPIO1,_GPIO1,_TOUCH1,_ADC1_CH0_5") (pintype "passive"))
    )
    (net (code "24") (name "/GPIO2") (class "Default")
      (node (ref "D6") (pin "1") (pinfunction "1_1") (pintype "passive"))
      (node (ref "J5") (pin "5") (pinfunction "5_5") (pintype "passive"))
      (node (ref "U7") (pin "6") (pinfunction "RTC_GPIO2,_GPIO2,_TOUCH2,_ADC1_CH1_6") (pintype "passive"))
    )
    (net (code "25") (name "/GPIO3") (class "Default")
      (node (ref "J5") (pin "6") (pinfunction "6_6") (pintype "passive"))
      (node (ref "U7") (pin "7") (pinfunction "RTC_GPIO3,_GPIO3,_TOUCH3,_ADC1_CH2_7") (pintype "passive"))
    )
    (net (code "26") (name "/GPIO4") (class "Default")
      (node (ref "J5") (pin "7") (pinfunction "7_7") (pintype "passive"))
      (node (ref "U7") (pin "8") (pinfunction "RTC_GPIO4,_GPIO4,_TOUCH4,_ADC1_CH3_8") (pintype "passive"))
    )
    (net (code "27") (name "/GPIO5") (class "Default")
      (node (ref "J5") (pin "8") (pinfunction "8_8") (pintype "passive"))
      (node (ref "U7") (pin "9") (pinfunction "RTC_GPIO5,_GPIO5,_TOUCH5,_ADC1_CH4_9") (pintype "passive"))
    )
    (net (code "28") (name "/GPIO6") (class "Default")
      (node (ref "J5") (pin "9") (pinfunction "9_9") (pintype "passive"))
      (node (ref "U7") (pin "10") (pinfunction "RTC_GPIO6,_GPIO6,_TOUCH6,_ADC1_CH5_10") (pintype "passive"))
    )
    (net (code "29") (name "/GPIO7") (class "Default")
      (node (ref "J5") (pin "10") (pinfunction "10_10") (pintype "passive"))
      (node (ref "U7") (pin "11") (pinfunction "RTC_GPIO7,_GPIO7,_TOUCH7,_ADC1_CH6_11") (pintype "passive"))
    )
    (net (code "30") (name "/GPIO8") (class "Default")
      (node (ref "J5") (pin "11") (pinfunction "11_11") (pintype "passive"))
      (node (ref "U7") (pin "12") (pinfunction "RTC_GPIO8,_GPIO8,_TOUCH8,_ADC1_CH7,_SUBSPICS1_12") (pintype "passive"))
    )
    (net (code "31") (name "/GPIO9") (class "Default")
      (node (ref "J5") (pin "12") (pinfunction "12_12") (pintype "passive"))
      (node (ref "U7") (pin "13") (pinfunction "RTC_GPIO9,_GPIO9,_TOUCH9,_ADC1_CH8,_FSPIHD,_SUBSPIHD_13") (pintype "passive"))
    )
    (net (code "32") (name "/GPIO10") (class "Default")
      (node (ref "J5") (pin "13") (pinfunction "13_13") (pintype "passive"))
      (node (ref "U7") (pin "14") (pinfunction "RTC_GPIO10,_GPIO10,_TOUCH10,_ADC1_CH9,_FSPICS0,_FSPIIO4,SUBSPICS0_14") (pintype "passive"))
    )
    (net (code "33") (name "/GPIO11") (class "Default")
      (node (ref "J5") (pin "14") (pinfunction "14_14") (pintype "passive"))
      (node (ref "U7") (pin "15") (pinfunction "RTC_GPIO11,_GPIO11,_TOUCH11,_ADC2_CH0,_FSPID,_FSPIIO5,_SUBSPID_15") (pintype "passive"))
    )
    (net (code "34") (name "/GPIO12") (class "Default")
      (node (ref "J5") (pin "15") (pinfunction "15_15") (pintype "passive"))
      (node (ref "U7") (pin "16") (pinfunction "RTC_GPIO12,_GPIO12,_TOUCH12,_ADC2_CH1,_FSPICLK,_FSPIIO6,_SUBSPICLK_16") (pintype "passive"))
    )
    (net (code "35") (name "/GPIO13") (class "Default")
      (node (ref "J5") (pin "16") (pinfunction "16_16") (pintype "passive"))
      (node (ref "U7") (pin "17") (pinfunction "RTC_GPIO13,_GPIO13,_TOUCH13,_ADC2_CH2,_FSPIQ,_FSPIIO7,_SUBSPIQ_17") (pintype "passive"))
    )
    (net (code "36") (name "/GPIO14") (class "Default")
      (node (ref "J5") (pin "17") (pinfunction "17_17") (pintype "passive"))
      (node (ref "U7") (pin "18") (pinfunction "RTC_GPIO14,_GPIO14,_TOUCH14,_ADC2_CH3,_FSPIWP,_FSPIDQS,_SUBSPIWP_18") (pintype "passive"))
    )
    (net (code "37") (name "/GPIO15") (class "Default")
      (node (ref "J5") (pin "18") (pinfunction "18_18") (pintype "passive"))
      (node (ref "U7") (pin "19") (pinfunction "RTC_GPIO15,_GPIO15,_U0RTS,_ADC2_CH4,_XTAL_32K_P_19") (pintype "passive"))
    )
    (net (code "38") (name "/GPIO16") (class "Default")
      (node (ref "J5") (pin "19") (pinfunction "19_19") (pintype "passive"))
      (node (ref "U7") (pin "20") (pinfunction "RTC_GPIO16,_GPIO16,_U0CTS,_ADC2_CH5,_XTAL_32K_N_20") (pintype "passive"))
    )
    (net (code "39") (name "/GPIO17") (class "Default")
      (node (ref "J5") (pin "20") (pinfunction "20_20") (pintype "passive"))
      (node (ref "U7") (pin "21") (pinfunction "RTC_GPIO17,_GPIO17,_U1TXD,_ADC2_CH6_21") (pintype "passive"))
    )
    (net (code "40") (name "/GPIO18") (class "Default")
      (node (ref "J5") (pin "21") (pinfunction "21_21") (pintype "passive"))
      (node (ref "U7") (pin "22") (pinfunction "RTC_GPIO18,_GPIO18,_U1RXD,_ADC2_CH7,_CLK_OUT3_22") (pintype "passive"))
    )
    (net (code "41") (name "/GPIO21") (class "Default")
      (node (ref "J6") (pin "19") (pinfunction "19_19") (pintype "passive"))
      (node (ref "U7") (pin "25") (pinfunction "RTC_GPIO21,_GPIO21_25") (pintype "passive"))
    )
    (net (code "42") (name "/GPIO26") (class "Default")
      (node (ref "J6") (pin "18") (pinfunction "18_18") (pintype "passive"))
      (node (ref "U7") (pin "26") (pinfunction "SPICS1,_GPIO26_26") (pintype "passive"))
    )
    (net (code "43") (name "/GPIO33") (class "Default")
      (node (ref "J6") (pin "17") (pinfunction "17_17") (pintype "passive"))
      (node (ref "U7") (pin "28") (pinfunction "SPIIO4,_GPIO33,_FSPIHD,_SUBSPIHD_28") (pintype "passive"))
    )
    (net (code "44") (name "/GPIO34") (class "Default")
      (node (ref "J6") (pin "16") (pinfunction "16_16") (pintype "passive"))
      (node (ref "U7") (pin "29") (pinfunction "SPIIO5,_GPIO34,_FSPICS0,_SUBSPICS0_29") (pintype "passive"))
    )
    (net (code "45") (name "/GPIO35") (class "Default")
      (node (ref "J6") (pin "15") (pinfunction "15_15") (pintype "passive"))
      (node (ref "U7") (pin "31") (pinfunction "SPIIO6,_GPIO35,_FSPID,_SUBSPID_31") (pintype "passive"))
    )
    (net (code "46") (name "/GPIO36") (class "Default")
      (node (ref "J6") (pin "14") (pinfunction "14_14") (pintype "passive"))
      (node (ref "U7") (pin "32") (pinfunction "SPIIO7,_GPIO36,_FSPICLK,_SUBSPICLK_32") (pintype "passive"))
    )
    (net (code "47") (name "/GPIO37") (class "Default")
      (node (ref "J6") (pin "13") (pinfunction "13_13") (pintype "passive"))
      (node (ref "U7") (pin "33") (pinfunction "SPIDQS,_GPIO37,_FSPIQ,_SUBSPIQ_33") (pintype "passive"))
    )
    (net (code "48") (name "/GPIO38") (class "Default")
      (node (ref "J6") (pin "12") (pinfunction "12_12") (pintype "passive"))
      (node (ref "U7") (pin "34") (pinfunction "GPIO38,_FSPIWP,_SUBSPIWP_34") (pintype "passive"))
    )
    (net (code "49") (name "/GPIO39") (class "Default")
      (node (ref "J6") (pin "11") (pinfunction "11_11") (pintype "passive"))
      (node (ref "U7") (pin "35") (pinfunction "MTCK,_GPIO39,_CLK_OUT3,_SUBSPICS1_35") (pintype "passive"))
    )
    (net (code "50") (name "/GPIO40") (class "Default")
      (node (ref "J6") (pin "10") (pinfunction "10_10") (pintype "passive"))
      (node (ref "U7") (pin "36") (pinfunction "MTDO,_GPIO40,_CLK_OUT2_36") (pintype "passive"))
    )
    (net (code "51") (name "/GPIO41") (class "Default")
      (node (ref "J6") (pin "9") (pinfunction "9_9") (pintype "passive"))
      (node (ref "U7") (pin "37") (pinfunction "MTDI,_GPIO41,_CLK_OUT1_37") (pintype "passive"))
    )
    (net (code "52") (name "/GPIO42") (class "Default")
      (node (ref "J6") (pin "8") (pinfunction "8_8") (pintype "passive"))
      (node (ref "U7") (pin "38") (pinfunction "MTMS,_GPIO42_38") (pintype "passive"))
    )
    (net (code "53") (name "/GPIO45") (class "Default")
      (node (ref "J6") (pin "5") (pinfunction "5_5") (pintype "passive"))
      (node (ref "U7") (pin "41") (pinfunction "GPIO45_41") (pintype "passive"))
    )
    (net (code "54") (name "/GPIO46") (class "Default")
      (node (ref "J6") (pin "4") (pinfunction "4_4") (pintype "passive"))
      (node (ref "U7") (pin "44") (pinfunction "GPIO46_44") (pintype "passive"))
    )
    (net (code "55") (name "/GPIO47") (class "Default")
      (node (ref "J6") (pin "23") (pinfunction "23_23") (pintype "passive"))
      (node (ref "U7") (pin "27") (pinfunction "SPICLK_P_DIFF,_GPIO47,_SUBSPICLK_P_DIFF_27") (pintype "passive"))
    )
    (net (code "56") (name "/GPIO48") (class "Default")
      (node (ref "J6") (pin "22") (pinfunction "22_22") (pintype "passive"))
      (node (ref "U7") (pin "30") (pinfunction "SPICLK_N_DIFF,_GPIO48,_SUBSPICLK_N_DIFF_30") (pintype "passive"))
    )
    (net (code "57") (name "/RTS_FTDI") (class "Default")
      (node (ref "Q1") (pin "2") (pinfunction "E_2") (pintype "passive"))
      (node (ref "R42") (pin "1") (pinfunction "1_1") (pintype "passive"))
      (node (ref "U5") (pin "19") (pinfunction "~{RTS}_19") (pintype "output"))
    )
    (net (code "58") (name "/RXD_FTDI") (class "Default")
      (node (ref "R44") (pin "2") (pinfunction "2_2") (pintype "passive"))
      (node (ref "U5") (pin "1") (pinfunction "RXD_1") (pintype "passive"))
    )
    (net (code "59") (name "/TXD_FTDI") (class "Default")
      (node (ref "R45") (pin "2") (pinfunction "2_2") (pintype "passive"))
      (node (ref "U5") (pin "17") (pinfunction "TXD_17") (pintype "output"))
    )
    (net (code "60") (name "/U0RXD") (class "Default")
      (node (ref "J6") (pin "6") (pinfunction "6_6") (pintype "passive"))
      (node (ref "R45") (pin "1") (pinfunction "1_1") (pintype "passive"))
      (node (ref "U7") (pin "40") (pinfunction "U0RXD,_GPIO44,_CLK_OUT2_40") (pintype "passive"))
    )
    (net (code "61") (name "/U0TXD") (class "Default")
      (node (ref "J6") (pin "7") (pinfunction "7_7") (pintype "passive"))
      (node (ref "R44") (pin "1") (pinfunction "1_1") (pintype "passive"))
      (node (ref "U7") (pin "39") (pinfunction "U0TXD,_GPIO43,_CLK_OUT1_39") (pintype "passive"))
    )
    (net (code "62") (name "/VBUS_SENSE") (class "Default")
      (node (ref "R33") (pin "1") (pinfunction "1_1") (pintype "passive"))
      (node (ref "R36") (pin "2") (pinfunction "2_2") (pintype "passive"))
      (node (ref "U5") (pin "16") (pinfunction "CBUS3_16") (pintype "passive"))
    )
    (net (code "63") (name "GND") (class "Default")
      (node (ref "C26") (pin "1") (pinfunction "1_1") (pintype "passive"))
      (node (ref "C27") (pin "1") (pinfunction "1_1") (pintype "passive"))
      (node (ref "C28") (pin "1") (pinfunction "1_1") (pintype "passive"))
      (node (ref "C29") (pin "1") (pinfunction "1_1") (pintype "passive"))
      (node (ref "C30") (pin "1") (pinfunction "1_1") (pintype "passive"))
      (node (ref "C31") (pin "1") (pinfunction "1_1") (pintype "passive"))
      (node (ref "C32") (pin "1") (pinfunction "1_1") (pintype "passive"))
      (node (ref "C33") (pin "1") (pinfunction "1_1") (pintype "passive"))
      (node (ref "C34") (pin "1") (pinfunction "1_1") (pintype "passive"))
      (node (ref "C35") (pin "1") (pinfunction "1_1") (pintype "passive"))
      (node (ref "C36") (pin "1") (pinfunction "1_1") (pintype "passive"))
      (node (ref "C37") (pin "1") (pinfunction "1_1") (pintype "passive"))
      (node (ref "C38") (pin "1") (pinfunction "1_1") (pintype "passive"))
      (node (ref "C39") (pin "1") (pinfunction "1_1") (pintype "passive"))
      (node (ref "C40") (pin "1") (pinfunction "1_1") (pintype "passive"))
      (node (ref "C41") (pin "1") (pinfunction "1_1") (pintype "passive"))
      (node (ref "C42") (pin "1") (pinfunction "1_1") (pintype "passive"))
      (node (ref "D2") (pin "1") (pinfunction "1_1") (pintype "passive"))
      (node (ref "D3") (pin "1") (pinfunction "1_1") (pintype "passive"))
      (node (ref "D4") (pin "1") (pinfunction "1_1") (pintype "passive"))
      (node (ref "D5") (pin "1") (pinfunction "1_1") (pintype "passive"))
      (node (ref "D7") (pin "1") (pinfunction "1_1") (pintype "passive"))
      (node (ref "D8") (pin "1") (pinfunction "1_1") (pintype "passive"))
      (node (ref "D9") (pin "1") (pinfunction "1_1") (pintype "passive"))
      (node (ref "J4") (pin "A1B12") (pinfunction "GND_A1B12_A1B12") (pintype "passive"))
      (node (ref "J4") (pin "B1A12") (pinfunction "GND_B1A12_B1A12") (pintype "passive"))
      (node (ref "J4") (pin "S1") (pinfunction "SHIELD_1_S1") (pintype "passive"))
      (node (ref "J4") (pin "S2") (pinfunction "SHIELD_2_S2") (pintype "passive"))
      (node (ref "J4") (pin "S3") (pinfunction "SHIELD_3_S3") (pintype "passive"))
      (node (ref "J4") (pin "S4") (pinfunction "SHIELD_4_S4") (pintype "passive"))
      (node (ref "J5") (pin "1") (pinfunction "1_1") (pintype "passive"))
      (node (ref "J5") (pin "23") (pinfunction "23_23") (pintype "passive"))
      (node (ref "J6") (pin "2") (pinfunction "2_2") (pintype "passive"))
      (node (ref "J6") (pin "24") (pinfunction "24_24") (pintype "passive"))
      (node (ref "J7") (pin "A1B12") (pinfunction "GND_A1B12_A1B12") (pintype "passive"))
      (node (ref "J7") (pin "B1A12") (pinfunction "GND_B1A12_B1A12") (pintype "passive"))
      (node (ref "J7") (pin "S1") (pinfunction "SHIELD_1_S1") (pintype "passive"))
      (node (ref "J7") (pin "S2") (pinfunction "SHIELD_2_S2") (pintype "passive"))
      (node (ref "J7") (pin "S3") (pinfunction "SHIELD_3_S3") (pintype "passive"))
      (node (ref "J7") (pin "S4") (pinfunction "SHIELD_4_S4") (pintype "passive"))
      (node (ref "R32") (pin "2") (pinfunction "2_2") (pintype "passive"))
      (node (ref "R34") (pin "2") (pinfunction "2_2") (pintype "passive"))
      (node (ref "R35") (pin "2") (pinfunction "2_2") (pintype "passive"))
      (node (ref "R36") (pin "1") (pinfunction "1_1") (pintype "passive"))
      (node (ref "R39") (pin "2") (pinfunction "2_2") (pintype "passive"))
      (node (ref "R40") (pin "2") (pinfunction "2_2") (pintype "passive"))
      (node (ref "SW3") (pin "3") (pinfunction "3_3") (pintype "passive"))
      (node (ref "SW3") (pin "4") (pinfunction "4_4") (pintype "passive"))
      (node (ref "SW4") (pin "3") (pinfunction "3_3") (pintype "passive"))
      (node (ref "SW4") (pin "4") (pinfunction "4_4") (pintype "passive"))
      (node (ref "U5") (pin "13") (pinfunction "GND_13") (pintype "passive"))
      (node (ref "U5") (pin "21") (pinfunction "GND_21") (pintype "passive"))
      (node (ref "U5") (pin "3") (pinfunction "GND_3") (pintype "passive"))
      (node (ref "U6") (pin "2") (pinfunction "GND_2") (pintype "power_in"))
      (node (ref "U6") (pin "4") (pinfunction "GND_4") (pintype "power_in"))
      (node (ref "U7") (pin "1") (pinfunction "GND_1_1") (pintype "passive"))
      (node (ref "U7") (pin "2") (pinfunction "GND_2_2") (pintype "passive"))
      (node (ref "U7") (pin "42") (pinfunction "GND_42_42") (pintype "passive"))
      (node (ref "U7") (pin "43") (pinfunction "GND_43_43") (pintype "passive"))
      (node (ref "U7") (pin "46") (pinfunction "GND_46_46") (pintype "passive"))
      (node (ref "U7") (pin "47") (pinfunction "GND_47_47") (pintype "passive"))
      (node (ref "U7") (pin "48") (pinfunction "GND_48_48") (pintype "passive"))
      (node (ref "U7") (pin "49") (pinfunction "GND_49_49") (pintype "passive"))
      (node (ref "U7") (pin "50") (pinfunction "GND_50_50") (pintype "passive"))
      (node (ref "U7") (pin "51") (pinfunction "GND_51_51") (pintype "passive"))
      (node (ref "U7") (pin "52") (pinfunction "GND_52_52") (pintype "passive"))
      (node (ref "U7") (pin "53") (pinfunction "GND_53_53") (pintype "passive"))
      (node (ref "U7") (pin "54") (pinfunction "GND_54_54") (pintype "passive"))
      (node (ref "U7") (pin "55") (pinfunction "GND_55_55") (pintype "passive"))
      (node (ref "U7") (pin "56") (pinfunction "GND_56_56") (pintype "passive"))
      (node (ref "U7") (pin "57") (pinfunction "GND_57_57") (pintype "passive"))
      (node (ref "U7") (pin "58") (pinfunction "GND_58_58") (pintype "passive"))
      (node (ref "U7") (pin "59") (pinfunction "GND_59_59") (pintype "passive"))
      (node (ref "U7") (pin "60") (pinfunction "GND_60_60") (pintype "passive"))
      (node (ref "U7") (pin "61") (pinfunction "GND_61_61") (pintype "passive"))
      (node (ref "U7") (pin "62") (pinfunction "GND_62_62") (pintype "passive"))
      (node (ref "U7") (pin "63") (pinfunction "GND_63_63") (pintype "passive"))
      (node (ref "U7") (pin "64") (pinfunction "GND_64_64") (pintype "passive"))
      (node (ref "U7") (pin "65") (pinfunction "GND_65_65") (pintype "passive"))
      (node (ref "U7") (pin "66") (pinfunction "GND_66_66") (pintype "passive"))
      (node (ref "U7") (pin "67") (pinfunction "GND_67_67") (pintype "passive"))
      (node (ref "U7") (pin "68") (pinfunction "GND_68_68") (pintype "passive"))
      (node (ref "U7") (pin "69") (pinfunction "GND_69_69") (pintype "passive"))
      (node (ref "U7") (pin "70") (pinfunction "GND_70_70") (pintype "passive"))
      (node (ref "U7") (pin "71") (pinfunction "GND_71_71") (pintype "passive"))
      (node (ref "U7") (pin "72") (pinfunction "GND_72_72") (pintype "passive"))
      (node (ref "U7") (pin "73") (pinfunction "GND_73_73") (pintype "passive"))
    )
    (net (code "64") (name "Net-(D5-Pad2)") (class "Default")
      (node (ref "D5") (pin "2") (pinfunction "2_2") (pintype "passive"))
      (node (ref "R37") (pin "1") (pinfunction "1_1") (pintype "passive"))
    )
    (net (code "65") (name "Net-(D6-Pad2)") (class "Default")
      (node (ref "D6") (pin "2") (pinfunction "2_2") (pintype "passive"))
      (node (ref "R38") (pin "1") (pinfunction "1_1") (pintype "passive"))
    )
    (net (code "66") (name "Net-(J4-CC1)") (class "Default")
      (node (ref "J4") (pin "A5") (pinfunction "CC1_A5") (pintype "passive"))
      (node (ref "R35") (pin "1") (pinfunction "1_1") (pintype "passive"))
    )
    (net (code "67") (name "Net-(J4-CC2)") (class "Default")
      (node (ref "J4") (pin "B5") (pinfunction "CC2_B5") (pintype "passive"))
      (node (ref "R34") (pin "1") (pinfunction "1_1") (pintype "passive"))
    )
    (net (code "68") (name "Net-(J7-CC1)") (class "Default")
      (node (ref "J7") (pin "A5") (pinfunction "CC1_A5") (pintype "passive"))
      (node (ref "R40") (pin "1") (pinfunction "1_1") (pintype "passive"))
    )
    (net (code "69") (name "Net-(J7-CC2)") (class "Default")
      (node (ref "J7") (pin "B5") (pinfunction "CC2_B5") (pintype "passive"))
      (node (ref "R39") (pin "1") (pinfunction "1_1") (pintype "passive"))
    )
    (net (code "70") (name "Net-(Q1-B)") (class "Default")
      (node (ref "Q1") (pin "1") (pinfunction "B_1") (pintype "passive"))
      (node (ref "R41") (pin "2") (pinfunction "2_2") (pintype "passive"))
    )
    (net (code "71") (name "Net-(Q2-B)") (class "Default")
      (node (ref "Q2") (pin "1") (pinfunction "B_1") (pintype "passive"))
      (node (ref "R42") (pin "2") (pinfunction "2_2") (pintype "passive"))
    )
    (net (code "72") (name "Net-(U5-CBUS0)") (class "Default")
      (node (ref "R32") (pin "1") (pinfunction "1_1") (pintype "passive"))
      (node (ref "U5") (pin "15") (pinfunction "CBUS0_15") (pintype "passive"))
    )
    (net (code "73") (name "Net-(U5-VCC)") (class "Default")
      (node (ref "C27") (pin "2") (pinfunction "2_2") (pintype "passive"))
      (node (ref "C28") (pin "2") (pinfunction "2_2") (pintype "passive"))
      (node (ref "R26") (pin "2") (pinfunction "2_2") (pintype "passive"))
      (node (ref "R27") (pin "2") (pinfunction "2_2") (pintype "passive"))
      (node (ref "U5") (pin "12") (pinfunction "VCC_12") (pintype "passive"))
    )
    (net (code "74") (name "unconnected-(J4-SBU1-PadA8)") (class "Default")
      (node (ref "J4") (pin "A8") (pinfunction "SBU1_A8") (pintype "passive+no_connect"))
    )
    (net (code "75") (name "unconnected-(J4-SBU2-PadB8)") (class "Default")
      (node (ref "J4") (pin "B8") (pinfunction "SBU2_B8") (pintype "passive+no_connect"))
    )
    (net (code "76") (name "unconnected-(J5-Pad24)") (class "Default")
      (node (ref "J5") (pin "24") (pinfunction "24_24") (pintype "passive+no_connect"))
    )
    (net (code "77") (name "unconnected-(J7-SBU1-PadA8)") (class "Default")
      (node (ref "J7") (pin "A8") (pinfunction "SBU1_A8") (pintype "passive+no_connect"))
    )
    (net (code "78") (name "unconnected-(J7-SBU2-PadB8)") (class "Default")
      (node (ref "J7") (pin "B8") (pinfunction "SBU2_B8") (pintype "passive+no_connect"))
    )
    (net (code "79") (name "unconnected-(U5-CBUS1-Pad14)") (class "Default")
      (node (ref "U5") (pin "14") (pinfunction "CBUS1_14") (pintype "passive+no_connect"))
    )
    (net (code "80") (name "unconnected-(U5-CBUS2-Pad7)") (class "Default")
      (node (ref "U5") (pin "7") (pinfunction "CBUS2_7") (pintype "passive+no_connect"))
    )
    (net (code "81") (name "unconnected-(U5-~{CTS}-Pad6)") (class "Default")
      (node (ref "U5") (pin "6") (pinfunction "~{CTS}_6") (pintype "input+no_connect"))
    )
    (net (code "82") (name "unconnected-(U5-~{DCD}-Pad5)") (class "Default")
      (node (ref "U5") (pin "5") (pinfunction "~{DCD}_5") (pintype "input+no_connect"))
    )
    (net (code "83") (name "unconnected-(U5-~{DSR}-Pad4)") (class "Default")
      (node (ref "U5") (pin "4") (pinfunction "~{DSR}_4") (pintype "input+no_connect"))
    )
    (net (code "84") (name "unconnected-(U5-~{RI}-Pad2)") (class "Default")
      (node (ref "U5") (pin "2") (pinfunction "~{RI}_2") (pintype "input+no_connect"))
    )
  )
)
